# PCB-AC2SL.net
KiCad netlist of a schematic drawn in EAGLE
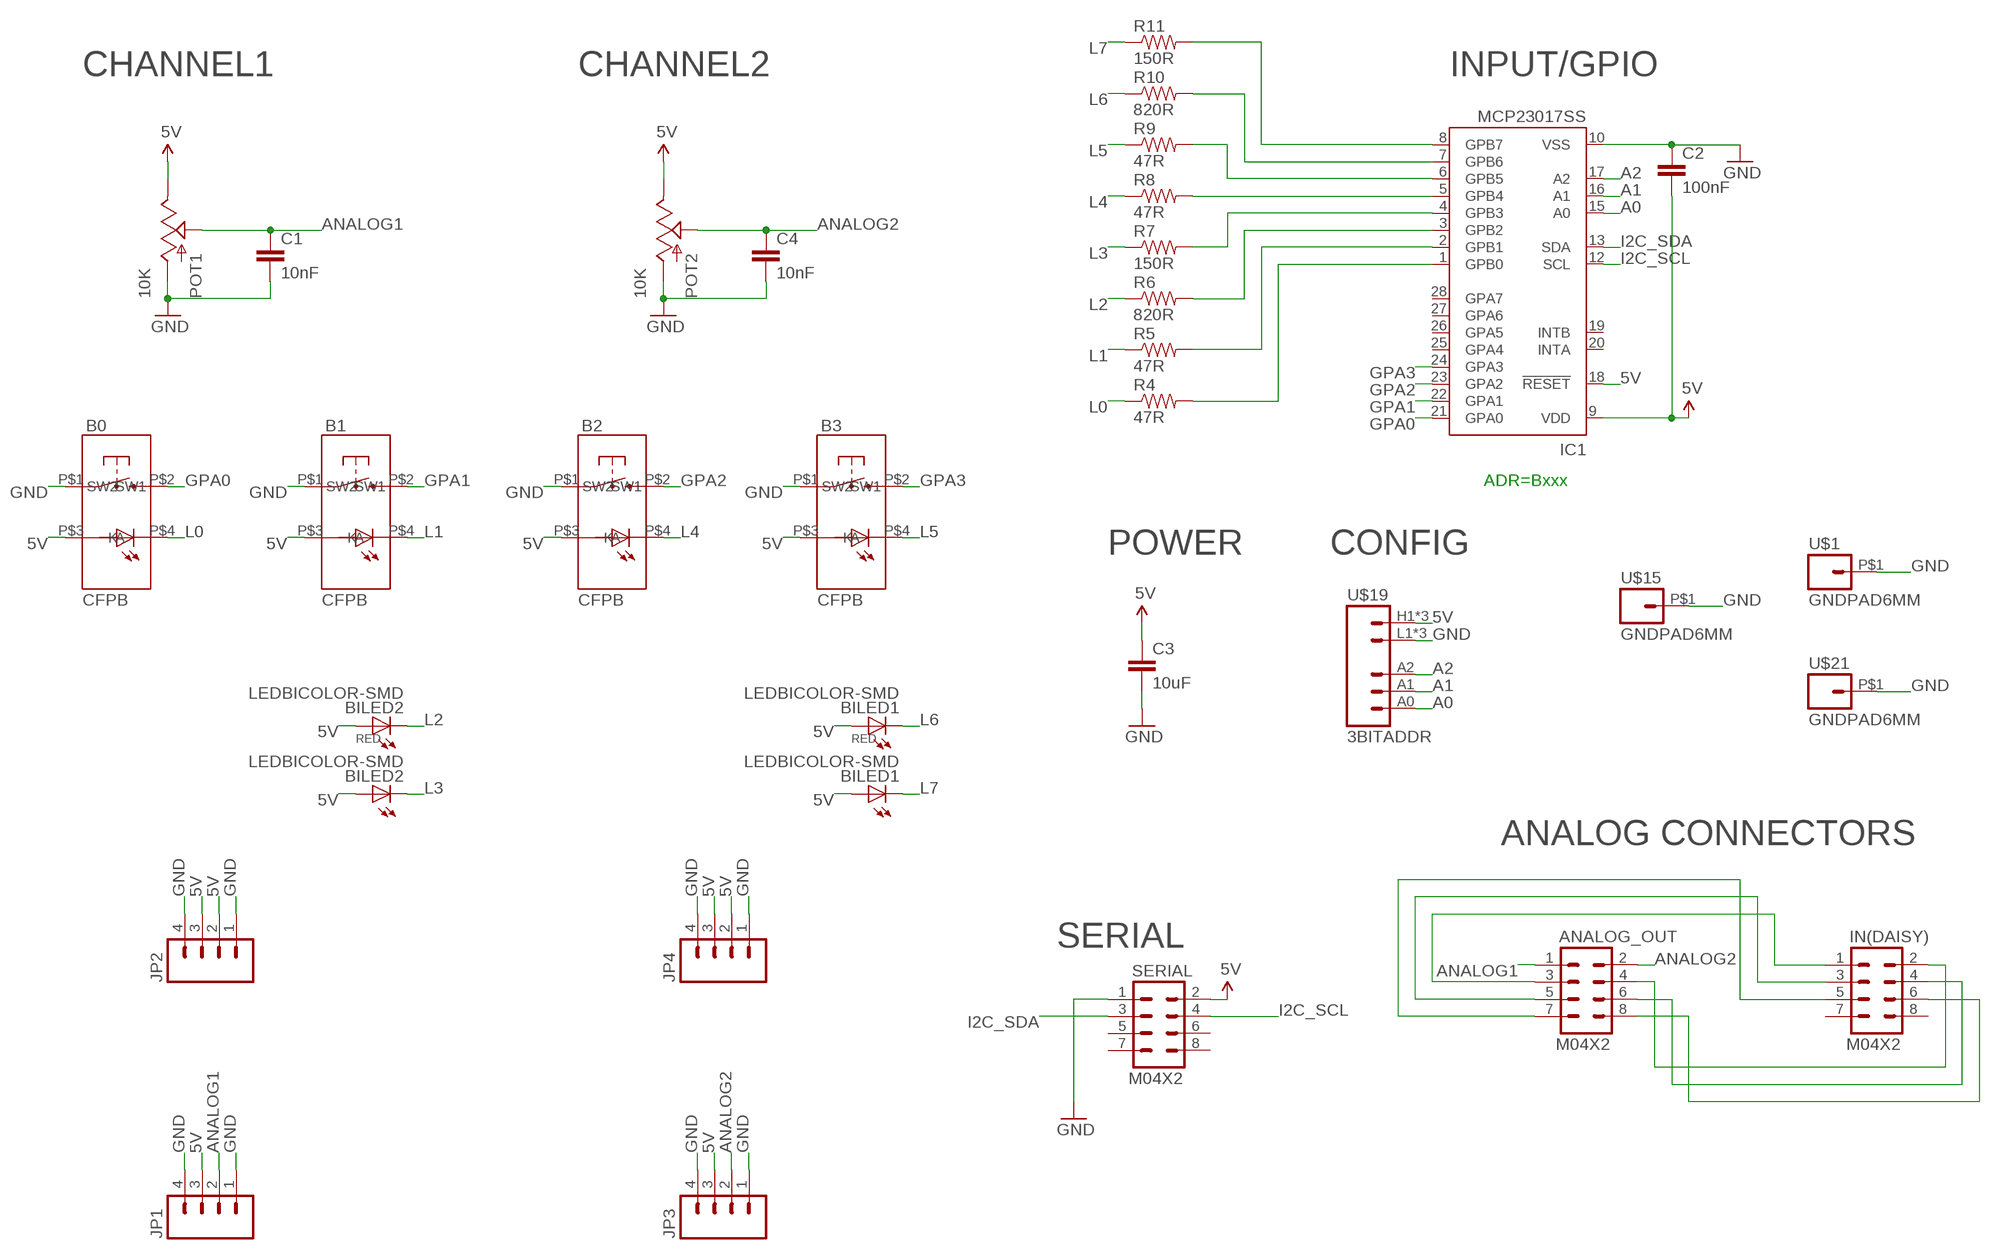
[diagram p0: schematic, sheet 1]

(export (version "E")
  (design (tool "Eeschema 10.0.6"))
  (components
    (comp (ref "ANALOG_OUT")
      (value "M04X2")
      (footprint "eagle-import:2X4")
      (libsource (lib "eagle-import") (part "M04X2"))
    )
    (comp (ref "B0")
      (value "CFPB")
      (footprint "eagle-import:CFPB-6_9MM")
      (libsource (lib "eagle-import") (part "CFPB"))
    )
    (comp (ref "B1")
      (value "CFPB")
      (footprint "eagle-import:CFPB-6_9MM")
      (libsource (lib "eagle-import") (part "CFPB"))
    )
    (comp (ref "B2")
      (value "CFPB")
      (footprint "eagle-import:CFPB-6_9MM")
      (libsource (lib "eagle-import") (part "CFPB"))
    )
    (comp (ref "B3")
      (value "CFPB")
      (footprint "eagle-import:CFPB-6_9MM")
      (libsource (lib "eagle-import") (part "CFPB"))
    )
    (comp (ref "BILED1")
      (value "LEDBICOLOR-SMD")
      (footprint "eagle-import:LEDBICOLOR-SMD")
      (libsource (lib "eagle-import") (part "LEDBICOLOR-SMD"))
    )
    (comp (ref "BILED2")
      (value "LEDBICOLOR-SMD")
      (footprint "eagle-import:LEDBICOLOR-SMD")
      (libsource (lib "eagle-import") (part "LEDBICOLOR-SMD"))
    )
    (comp (ref "C1")
      (value "10nF")
      (footprint "eagle-import:0603-CAP")
      (libsource (lib "eagle-import") (part "CAP0603-CAP"))
    )
    (comp (ref "C2")
      (value "100nF")
      (footprint "eagle-import:0603-CAP")
      (libsource (lib "eagle-import") (part "CAP0603-CAP"))
    )
    (comp (ref "C3")
      (value "10uF")
      (footprint "eagle-import:0805")
      (libsource (lib "eagle-import") (part "CAP0805"))
    )
    (comp (ref "C4")
      (value "10nF")
      (footprint "eagle-import:0603-CAP")
      (libsource (lib "eagle-import") (part "CAP0603-CAP"))
    )
    (comp (ref "IC1")
      (value "MCP23017SS")
      (footprint "eagle-import:SSOP28")
      (fields
        (field (name "MF") "MICROCHIP")
        (field (name "MPN") "MCP23017-E/SS")
        (field (name "MPN_1") "MCP23017-E/SS")
        (field (name "OC_FARNELL") "1467674")
        (field (name "OC_NEWARK") "31K2960")
      )
      (libsource (lib "eagle-import") (part "MCP23017SS"))
    )
    (comp (ref "IN(DAISY)")
      (value "M04X2")
      (footprint "eagle-import:2X4")
      (libsource (lib "eagle-import") (part "M04X2"))
    )
    (comp (ref "JP1")
      (value "M04PTH")
      (footprint "eagle-import:1X04")
      (libsource (lib "eagle-import") (part "M04PTH"))
    )
    (comp (ref "JP2")
      (value "M04PTH")
      (footprint "eagle-import:1X04")
      (libsource (lib "eagle-import") (part "M04PTH"))
    )
    (comp (ref "JP3")
      (value "M04PTH")
      (footprint "eagle-import:1X04")
      (libsource (lib "eagle-import") (part "M04PTH"))
    )
    (comp (ref "JP4")
      (value "M04PTH")
      (footprint "eagle-import:1X04")
      (libsource (lib "eagle-import") (part "M04PTH"))
    )
    (comp (ref "POT1")
      (value "10K")
      (footprint "eagle-import:SLIDER45")
      (libsource (lib "eagle-import") (part "SLIDER45"))
    )
    (comp (ref "POT2")
      (value "10K")
      (footprint "eagle-import:SLIDER45")
      (libsource (lib "eagle-import") (part "SLIDER45"))
    )
    (comp (ref "R4")
      (value "47R")
      (footprint "eagle-import:0603-RES")
      (libsource (lib "eagle-import") (part "RESISTOR0603-RES"))
    )
    (comp (ref "R5")
      (value "47R")
      (footprint "eagle-import:0603-RES")
      (libsource (lib "eagle-import") (part "RESISTOR0603-RES"))
    )
    (comp (ref "R6")
      (value "820R")
      (footprint "eagle-import:0603-RES")
      (libsource (lib "eagle-import") (part "RESISTOR0603-RES"))
    )
    (comp (ref "R7")
      (value "150R")
      (footprint "eagle-import:0603-RES")
      (libsource (lib "eagle-import") (part "RESISTOR0603-RES"))
    )
    (comp (ref "R8")
      (value "47R")
      (footprint "eagle-import:0603-RES")
      (libsource (lib "eagle-import") (part "RESISTOR0603-RES"))
    )
    (comp (ref "R9")
      (value "47R")
      (footprint "eagle-import:0603-RES")
      (libsource (lib "eagle-import") (part "RESISTOR0603-RES"))
    )
    (comp (ref "R10")
      (value "820R")
      (footprint "eagle-import:0603-RES")
      (libsource (lib "eagle-import") (part "RESISTOR0603-RES"))
    )
    (comp (ref "R11")
      (value "150R")
      (footprint "eagle-import:0603-RES")
      (libsource (lib "eagle-import") (part "RESISTOR0603-RES"))
    )
    (comp (ref "SERIAL")
      (value "M04X2")
      (footprint "eagle-import:2X4")
      (libsource (lib "eagle-import") (part "M04X2"))
    )
    (comp (ref "U$1")
      (value "GNDPAD6MM")
      (footprint "eagle-import:3.2MMPAD6MM")
      (libsource (lib "eagle-import") (part "GNDPAD6MM"))
    )
    (comp (ref "U$15")
      (value "GNDPAD6MM")
      (footprint "eagle-import:3.2MMPAD6MM")
      (libsource (lib "eagle-import") (part "GNDPAD6MM"))
    )
    (comp (ref "U$19")
      (value "3BITADDR")
      (footprint "eagle-import:3BITADDR")
      (libsource (lib "eagle-import") (part "3BITADDR"))
    )
    (comp (ref "U$21")
      (value "GNDPAD6MM")
      (footprint "eagle-import:3.2MMPAD6MM")
      (libsource (lib "eagle-import") (part "GNDPAD6MM"))
    )
  )
  (nets
    (net (code "1") (name "5V") (class "Default")
      (node (ref "B0") (pin "P$3") (pinfunction "A_P$3") (pintype "bidirectional"))
      (node (ref "B1") (pin "P$3") (pinfunction "A_P$3") (pintype "bidirectional"))
      (node (ref "B2") (pin "P$3") (pinfunction "A_P$3") (pintype "bidirectional"))
      (node (ref "B3") (pin "P$3") (pinfunction "A_P$3") (pintype "bidirectional"))
      (node (ref "BILED1") (pin "P$1") (pinfunction "A_P$1") (pintype "passive"))
      (node (ref "BILED1") (pin "P$3") (pinfunction "A1_P$3") (pintype "passive"))
      (node (ref "BILED2") (pin "P$1") (pinfunction "A_P$1") (pintype "passive"))
      (node (ref "BILED2") (pin "P$3") (pinfunction "A1_P$3") (pintype "passive"))
      (node (ref "C2") (pin "2") (pinfunction "2_2") (pintype "passive"))
      (node (ref "C3") (pin "1") (pinfunction "1_1") (pintype "passive"))
      (node (ref "IC1") (pin "18") (pinfunction "~{RESET}_18") (pintype "input"))
      (node (ref "IC1") (pin "9") (pinfunction "VDD_9") (pintype "power_in"))
      (node (ref "JP1") (pin "3") (pinfunction "3_3") (pintype "passive"))
      (node (ref "JP2") (pin "2") (pinfunction "2_2") (pintype "passive"))
      (node (ref "JP2") (pin "3") (pinfunction "3_3") (pintype "passive"))
      (node (ref "JP3") (pin "3") (pinfunction "3_3") (pintype "passive"))
      (node (ref "JP4") (pin "2") (pinfunction "2_2") (pintype "passive"))
      (node (ref "JP4") (pin "3") (pinfunction "3_3") (pintype "passive"))
      (node (ref "POT1") (pin "1") (pinfunction "E_1") (pintype "passive"))
      (node (ref "POT2") (pin "1") (pinfunction "E_1") (pintype "passive"))
      (node (ref "SERIAL") (pin "2") (pinfunction "2_2") (pintype "passive"))
      (node (ref "U$19") (pin "H1") (pinfunction "VCC_H1") (pintype "passive"))
      (node (ref "U$19") (pin "H2") (pinfunction "VCC_H2") (pintype "passive"))
      (node (ref "U$19") (pin "H3") (pinfunction "VCC_H3") (pintype "passive"))
    )
    (net (code "2") (name "A0") (class "Default")
      (node (ref "IC1") (pin "15") (pinfunction "A0_15") (pintype "input"))
      (node (ref "U$19") (pin "A0") (pinfunction "A0_A0") (pintype "passive"))
    )
    (net (code "3") (name "A1") (class "Default")
      (node (ref "IC1") (pin "16") (pinfunction "A1_16") (pintype "input"))
      (node (ref "U$19") (pin "A1") (pinfunction "A1_A1") (pintype "passive"))
    )
    (net (code "4") (name "A2") (class "Default")
      (node (ref "IC1") (pin "17") (pinfunction "A2_17") (pintype "input"))
      (node (ref "U$19") (pin "A2") (pinfunction "A2_A2") (pintype "passive"))
    )
    (net (code "5") (name "ANALOG1") (class "Default")
      (node (ref "ANALOG_OUT") (pin "1") (pinfunction "1_1") (pintype "passive"))
      (node (ref "C1") (pin "1") (pinfunction "1_1") (pintype "passive"))
      (node (ref "JP1") (pin "2") (pinfunction "2_2") (pintype "passive"))
      (node (ref "POT1") (pin "2A") (pinfunction "S_2A") (pintype "passive"))
    )
    (net (code "6") (name "ANALOG2") (class "Default")
      (node (ref "ANALOG_OUT") (pin "2") (pinfunction "2_2") (pintype "passive"))
      (node (ref "C4") (pin "1") (pinfunction "1_1") (pintype "passive"))
      (node (ref "JP3") (pin "2") (pinfunction "2_2") (pintype "passive"))
      (node (ref "POT2") (pin "2A") (pinfunction "S_2A") (pintype "passive"))
    )
    (net (code "7") (name "GND") (class "Default")
      (node (ref "B0") (pin "P$1") (pinfunction "SW1_P$1") (pintype "bidirectional"))
      (node (ref "B1") (pin "P$1") (pinfunction "SW1_P$1") (pintype "bidirectional"))
      (node (ref "B2") (pin "P$1") (pinfunction "SW1_P$1") (pintype "bidirectional"))
      (node (ref "B3") (pin "P$1") (pinfunction "SW1_P$1") (pintype "bidirectional"))
      (node (ref "C1") (pin "2") (pinfunction "2_2") (pintype "passive"))
      (node (ref "C2") (pin "1") (pinfunction "1_1") (pintype "passive"))
      (node (ref "C3") (pin "2") (pinfunction "2_2") (pintype "passive"))
      (node (ref "C4") (pin "2") (pinfunction "2_2") (pintype "passive"))
      (node (ref "IC1") (pin "10") (pinfunction "VSS_10") (pintype "power_in"))
      (node (ref "JP1") (pin "1") (pinfunction "1_1") (pintype "passive"))
      (node (ref "JP1") (pin "4") (pinfunction "4_4") (pintype "passive"))
      (node (ref "JP2") (pin "1") (pinfunction "1_1") (pintype "passive"))
      (node (ref "JP2") (pin "4") (pinfunction "4_4") (pintype "passive"))
      (node (ref "JP3") (pin "1") (pinfunction "1_1") (pintype "passive"))
      (node (ref "JP3") (pin "4") (pinfunction "4_4") (pintype "passive"))
      (node (ref "JP4") (pin "1") (pinfunction "1_1") (pintype "passive"))
      (node (ref "JP4") (pin "4") (pinfunction "4_4") (pintype "passive"))
      (node (ref "POT1") (pin "3") (pinfunction "A_3") (pintype "passive"))
      (node (ref "POT2") (pin "3") (pinfunction "A_3") (pintype "passive"))
      (node (ref "SERIAL") (pin "1") (pinfunction "1_1") (pintype "passive"))
      (node (ref "U$1") (pin "P$1") (pinfunction "1_P$1") (pintype "passive"))
      (node (ref "U$15") (pin "P$1") (pinfunction "1_P$1") (pintype "passive"))
      (node (ref "U$19") (pin "L1") (pinfunction "GND_L1") (pintype "passive"))
      (node (ref "U$19") (pin "L2") (pinfunction "GND_L2") (pintype "passive"))
      (node (ref "U$19") (pin "L3") (pinfunction "GND_L3") (pintype "passive"))
      (node (ref "U$21") (pin "P$1") (pinfunction "1_P$1") (pintype "passive"))
    )
    (net (code "8") (name "GPA0") (class "Default")
      (node (ref "B0") (pin "P$2") (pinfunction "SW2_P$2") (pintype "bidirectional"))
      (node (ref "IC1") (pin "21") (pinfunction "GPA0_21") (pintype "bidirectional"))
    )
    (net (code "9") (name "GPA1") (class "Default")
      (node (ref "B1") (pin "P$2") (pinfunction "SW2_P$2") (pintype "bidirectional"))
      (node (ref "IC1") (pin "22") (pinfunction "GPA1_22") (pintype "bidirectional"))
    )
    (net (code "10") (name "GPA2") (class "Default")
      (node (ref "B2") (pin "P$2") (pinfunction "SW2_P$2") (pintype "bidirectional"))
      (node (ref "IC1") (pin "23") (pinfunction "GPA2_23") (pintype "bidirectional"))
    )
    (net (code "11") (name "GPA3") (class "Default")
      (node (ref "B3") (pin "P$2") (pinfunction "SW2_P$2") (pintype "bidirectional"))
      (node (ref "IC1") (pin "24") (pinfunction "GPA3_24") (pintype "bidirectional"))
    )
    (net (code "12") (name "I2C_SCL") (class "Default")
      (node (ref "IC1") (pin "12") (pinfunction "SCL_12") (pintype "input"))
      (node (ref "SERIAL") (pin "4") (pinfunction "4_4") (pintype "passive"))
    )
    (net (code "13") (name "I2C_SDA") (class "Default")
      (node (ref "IC1") (pin "13") (pinfunction "SDA_13") (pintype "bidirectional"))
      (node (ref "SERIAL") (pin "3") (pinfunction "3_3") (pintype "passive"))
    )
    (net (code "14") (name "L0") (class "Default")
      (node (ref "B0") (pin "P$4") (pinfunction "K_P$4") (pintype "bidirectional"))
      (node (ref "R4") (pin "1") (pinfunction "1_1") (pintype "passive"))
    )
    (net (code "15") (name "L1") (class "Default")
      (node (ref "B1") (pin "P$4") (pinfunction "K_P$4") (pintype "bidirectional"))
      (node (ref "R5") (pin "1") (pinfunction "1_1") (pintype "passive"))
    )
    (net (code "16") (name "L2") (class "Default")
      (node (ref "BILED2") (pin "P$2") (pinfunction "C_P$2") (pintype "passive"))
      (node (ref "R6") (pin "1") (pinfunction "1_1") (pintype "passive"))
    )
    (net (code "17") (name "L3") (class "Default")
      (node (ref "BILED2") (pin "P$4") (pinfunction "C1_P$4") (pintype "passive"))
      (node (ref "R7") (pin "1") (pinfunction "1_1") (pintype "passive"))
    )
    (net (code "18") (name "L4") (class "Default")
      (node (ref "B2") (pin "P$4") (pinfunction "K_P$4") (pintype "bidirectional"))
      (node (ref "R8") (pin "1") (pinfunction "1_1") (pintype "passive"))
    )
    (net (code "19") (name "L5") (class "Default")
      (node (ref "B3") (pin "P$4") (pinfunction "K_P$4") (pintype "bidirectional"))
      (node (ref "R9") (pin "1") (pinfunction "1_1") (pintype "passive"))
    )
    (net (code "20") (name "L6") (class "Default")
      (node (ref "BILED1") (pin "P$2") (pinfunction "C_P$2") (pintype "passive"))
      (node (ref "R10") (pin "1") (pinfunction "1_1") (pintype "passive"))
    )
    (net (code "21") (name "L7") (class "Default")
      (node (ref "BILED1") (pin "P$4") (pinfunction "C1_P$4") (pintype "passive"))
      (node (ref "R11") (pin "1") (pinfunction "1_1") (pintype "passive"))
    )
    (net (code "22") (name "Net-(ANALOG_OUT-Pad3)") (class "Default")
      (node (ref "ANALOG_OUT") (pin "3") (pinfunction "3_3") (pintype "passive"))
      (node (ref "IN(DAISY)") (pin "1") (pinfunction "1_1") (pintype "passive"))
    )
    (net (code "23") (name "Net-(ANALOG_OUT-Pad4)") (class "Default")
      (node (ref "ANALOG_OUT") (pin "4") (pinfunction "4_4") (pintype "passive"))
      (node (ref "IN(DAISY)") (pin "2") (pinfunction "2_2") (pintype "passive"))
    )
    (net (code "24") (name "Net-(ANALOG_OUT-Pad5)") (class "Default")
      (node (ref "ANALOG_OUT") (pin "5") (pinfunction "5_5") (pintype "passive"))
      (node (ref "IN(DAISY)") (pin "3") (pinfunction "3_3") (pintype "passive"))
    )
    (net (code "25") (name "Net-(ANALOG_OUT-Pad6)") (class "Default")
      (node (ref "ANALOG_OUT") (pin "6") (pinfunction "6_6") (pintype "passive"))
      (node (ref "IN(DAISY)") (pin "4") (pinfunction "4_4") (pintype "passive"))
    )
    (net (code "26") (name "Net-(ANALOG_OUT-Pad7)") (class "Default")
      (node (ref "ANALOG_OUT") (pin "7") (pinfunction "7_7") (pintype "passive"))
      (node (ref "IN(DAISY)") (pin "5") (pinfunction "5_5") (pintype "passive"))
    )
    (net (code "27") (name "Net-(ANALOG_OUT-Pad8)") (class "Default")
      (node (ref "ANALOG_OUT") (pin "8") (pinfunction "8_8") (pintype "passive"))
      (node (ref "IN(DAISY)") (pin "6") (pinfunction "6_6") (pintype "passive"))
    )
    (net (code "28") (name "Net-(IC1-GPB0)") (class "Default")
      (node (ref "IC1") (pin "1") (pinfunction "GPB0_1") (pintype "bidirectional"))
      (node (ref "R4") (pin "2") (pinfunction "2_2") (pintype "passive"))
    )
    (net (code "29") (name "Net-(IC1-GPB1)") (class "Default")
      (node (ref "IC1") (pin "2") (pinfunction "GPB1_2") (pintype "bidirectional"))
      (node (ref "R5") (pin "2") (pinfunction "2_2") (pintype "passive"))
    )
    (net (code "30") (name "Net-(IC1-GPB2)") (class "Default")
      (node (ref "IC1") (pin "3") (pinfunction "GPB2_3") (pintype "bidirectional"))
      (node (ref "R6") (pin "2") (pinfunction "2_2") (pintype "passive"))
    )
    (net (code "31") (name "Net-(IC1-GPB3)") (class "Default")
      (node (ref "IC1") (pin "4") (pinfunction "GPB3_4") (pintype "bidirectional"))
      (node (ref "R7") (pin "2") (pinfunction "2_2") (pintype "passive"))
    )
    (net (code "32") (name "Net-(IC1-GPB4)") (class "Default")
      (node (ref "IC1") (pin "5") (pinfunction "GPB4_5") (pintype "bidirectional"))
      (node (ref "R8") (pin "2") (pinfunction "2_2") (pintype "passive"))
    )
    (net (code "33") (name "Net-(IC1-GPB5)") (class "Default")
      (node (ref "IC1") (pin "6") (pinfunction "GPB5_6") (pintype "bidirectional"))
      (node (ref "R9") (pin "2") (pinfunction "2_2") (pintype "passive"))
    )
    (net (code "34") (name "Net-(IC1-GPB6)") (class "Default")
      (node (ref "IC1") (pin "7") (pinfunction "GPB6_7") (pintype "bidirectional"))
      (node (ref "R10") (pin "2") (pinfunction "2_2") (pintype "passive"))
    )
    (net (code "35") (name "Net-(IC1-GPB7)") (class "Default")
      (node (ref "IC1") (pin "8") (pinfunction "GPB7_8") (pintype "bidirectional"))
      (node (ref "R11") (pin "2") (pinfunction "2_2") (pintype "passive"))
    )
    (net (code "36") (name "unconnected-(IC1-GPA4-Pad25)") (class "Default")
      (node (ref "IC1") (pin "25") (pinfunction "GPA4_25") (pintype "bidirectional"))
    )
    (net (code "37") (name "unconnected-(IC1-GPA5-Pad26)") (class "Default")
      (node (ref "IC1") (pin "26") (pinfunction "GPA5_26") (pintype "bidirectional"))
    )
    (net (code "38") (name "unconnected-(IC1-GPA6-Pad27)") (class "Default")
      (node (ref "IC1") (pin "27") (pinfunction "GPA6_27") (pintype "bidirectional"))
    )
    (net (code "39") (name "unconnected-(IC1-GPA7-Pad28)") (class "Default")
      (node (ref "IC1") (pin "28") (pinfunction "GPA7_28") (pintype "bidirectional"))
    )
    (net (code "40") (name "unconnected-(IC1-INTA-Pad20)") (class "Default")
      (node (ref "IC1") (pin "20") (pinfunction "INTA_20") (pintype "output"))
    )
    (net (code "41") (name "unconnected-(IC1-INTB-Pad19)") (class "Default")
      (node (ref "IC1") (pin "19") (pinfunction "INTB_19") (pintype "output"))
    )
    (net (code "42") (name "unconnected-(IN(DAISY)-Pad7)") (class "Default")
      (node (ref "IN(DAISY)") (pin "7") (pinfunction "7_7") (pintype "passive"))
    )
    (net (code "43") (name "unconnected-(IN(DAISY)-Pad8)") (class "Default")
      (node (ref "IN(DAISY)") (pin "8") (pinfunction "8_8") (pintype "passive"))
    )
    (net (code "44") (name "unconnected-(SERIAL-Pad5)") (class "Default")
      (node (ref "SERIAL") (pin "5") (pinfunction "5_5") (pintype "passive"))
    )
    (net (code "45") (name "unconnected-(SERIAL-Pad6)") (class "Default")
      (node (ref "SERIAL") (pin "6") (pinfunction "6_6") (pintype "passive"))
    )
    (net (code "46") (name "unconnected-(SERIAL-Pad7)") (class "Default")
      (node (ref "SERIAL") (pin "7") (pinfunction "7_7") (pintype "passive"))
    )
    (net (code "47") (name "unconnected-(SERIAL-Pad8)") (class "Default")
      (node (ref "SERIAL") (pin "8") (pinfunction "8_8") (pintype "passive"))
    )
  )
)
